# Power_management.net
KiCad netlist of a schematic drawn in Altium Designer
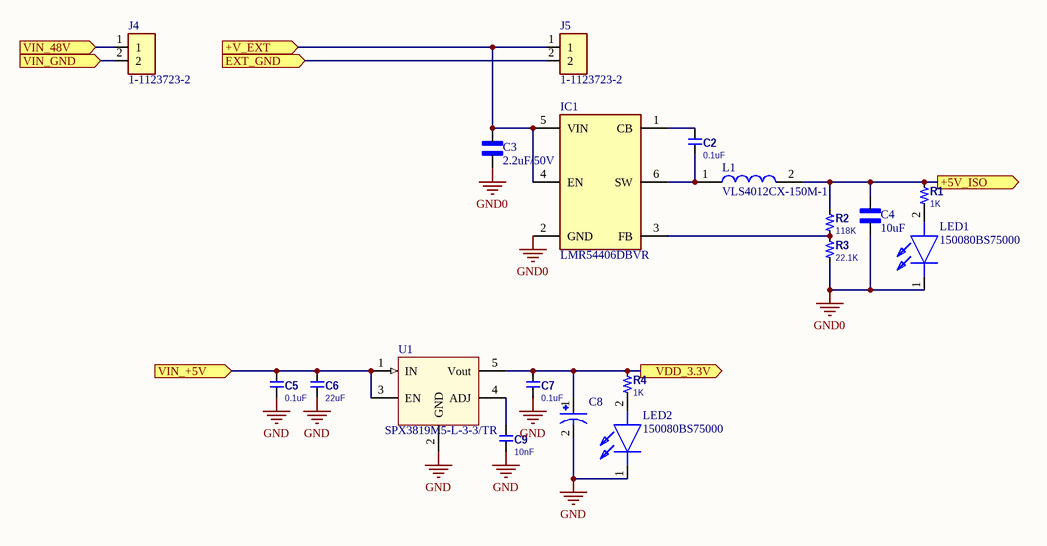
[diagram p0: Power_management.SchDoc]

(export (version "E")
  (design (tool "Eeschema 10.0.6"))
  (components
    (comp (ref "C2")
      (value "0.1uF")
      (footprint "0603-C")
      (description "CAP")
      (fields
        (field (name "MANUFACTURER") "TDK EPCOS")
        (field (name "MANUFACTURER PART NUMBER") "B37941K9105K62")
      )
      (libsource (lib "ESP32_IO_module") (part "CAP"))
    )
    (comp (ref "C3")
      (value "2.2uF/50V")
      (footprint "0805_C")
      (fields (field (name "MP") "LD03ZD475MAB2A"))
      (libsource (lib "IIOT_GATEWAY_MT7621") (part "CAP"))
    )
    (comp (ref "C4")
      (value "10uF")
      (footprint "0805_C")
      (fields (field (name "MP") "LD03ZD475MAB2A"))
      (libsource (lib "IIOT_GATEWAY_MT7621") (part "CAP"))
    )
    (comp (ref "C5")
      (value "0.1uF")
      (footprint "0603-C")
      (description "CAP")
      (fields
        (field (name "MANUFACTURER") "TDK EPCOS")
        (field (name "MANUFACTURER PART NUMBER") "B37941K9105K62")
      )
      (libsource (lib "Safety_Lock") (part "CAP"))
    )
    (comp (ref "C6")
      (value "22uF")
      (footprint "0603-C")
      (description "CAP")
      (fields
        (field (name "MANUFACTURER") "TDK EPCOS")
        (field (name "MANUFACTURER PART NUMBER") "B37941K9105K62")
      )
      (libsource (lib "Safety_Lock") (part "CAP"))
    )
    (comp (ref "C7")
      (value "0.1uF")
      (footprint "0603-C")
      (description "CAP")
      (fields
        (field (name "MANUFACTURER") "TDK EPCOS")
        (field (name "MANUFACTURER PART NUMBER") "B37941K9105K62")
      )
      (libsource (lib "Safety_Lock") (part "CAP"))
    )
    (comp (ref "C8")
      (value "T493X227K010BH6420_220uF")
      (footprint "CAPPM7343X430N")
      (fields (field (name "MP") "T493X227K010BH6420") (field (name "MF") "Kemet"))
      (libsource (lib "Safety_Lock") (part "T493X227K010BH6420_220uF"))
    )
    (comp (ref "C9")
      (value "10nF")
      (footprint "0603-C")
      (description "CAP")
      (fields
        (field (name "MANUFACTURER") "TDK EPCOS")
        (field (name "MANUFACTURER PART NUMBER") "B37941K9105K62")
      )
      (libsource (lib "Safety_Lock") (part "CAP"))
    )
    (comp (ref "IC1")
      (value "LMR54406DBVR")
      (footprint "SamacSys:SOT95P280X145-6N")
      (description "Integrated Circuit")
      (fields (field (name "MOUSER PART NUMBER") "595-LMR54406DBVR"))
      (libsource (lib "SamacSys") (part "LMR54406DBVR"))
    )
    (comp (ref "J4")
      (value "1-1123723-2")
      (footprint "TE_1-1123723-2")
      (description "3.96 EP HDR ASSY 2P_NATURAL_")
      (fields (field (name "MF") "TE Connectivity") (field (name "DIGI-KEY_PART_NUMBER") "A111830-ND"))
      (libsource (lib "IIOT_GATEWAY_MT7621") (part "1-1123723-2"))
    )
    (comp (ref "J5")
      (value "1-1123723-2")
      (footprint "TE_1-1123723-2")
      (description "3.96 EP HDR ASSY 2P_NATURAL_")
      (fields (field (name "MF") "TE Connectivity") (field (name "DIGI-KEY_PART_NUMBER") "A111830-ND"))
      (libsource (lib "IIOT_GATEWAY_MT7621") (part "1-1123723-2"))
    )
    (comp (ref "L1")
      (value "VLS4012CX-150M-1")
      (footprint "SamacSys:VLS4012")
      (description "Inductor")
      (fields (field (name "MOUSER PART NUMBER") "810-VLS4012CX150M1"))
      (libsource (lib "*") (part "VLS4012CX-150M-1"))
    )
    (comp (ref "LED1")
      (value "150080BS75000")
      (footprint "SamacSys:LEDC2012X80N")
      (description "LED")
      (fields (field (name "MOUSER PART NUMBER") "710-150080BS75000"))
      (libsource (lib "*") (part "150080BS75000"))
    )
    (comp (ref "LED2")
      (value "150080BS75000")
      (footprint "SamacSys:LEDC2012X80N")
      (description "LED")
      (fields (field (name "MOUSER PART NUMBER") "710-150080BS75000"))
      (libsource (lib "*") (part "150080BS75000"))
    )
    (comp (ref "R1")
      (value "1K")
      (footprint "0603-R")
      (fields
        (field (name "MANUFACTURER") "Panasonic")
        (field (name "MANUFACTURER PART NUMBER") "ERJ-8GEYJ621V")
        (field (name "TOLERANCE") "5%")
      )
      (libsource (lib "ESP32_IO_module") (part "Res_2"))
    )
    (comp (ref "R2")
      (value "118K")
      (footprint "0603-R")
      (fields
        (field (name "MANUFACTURER") "Panasonic")
        (field (name "MANUFACTURER PART NUMBER") "ERJ-8GEYJ621V")
        (field (name "TOLERANCE") "5%")
      )
      (libsource (lib "ESP32_IO_module") (part "Res_2"))
    )
    (comp (ref "R3")
      (value "22.1K")
      (footprint "0603-R")
      (fields
        (field (name "MANUFACTURER") "Panasonic")
        (field (name "MANUFACTURER PART NUMBER") "ERJ-8GEYJ621V")
        (field (name "TOLERANCE") "5%")
      )
      (libsource (lib "ESP32_IO_module") (part "Res_2"))
    )
    (comp (ref "R4")
      (value "1K")
      (footprint "0603-R")
      (fields
        (field (name "MANUFACTURER") "Panasonic")
        (field (name "MANUFACTURER PART NUMBER") "ERJ-8GEYJ621V")
        (field (name "TOLERANCE") "5%")
      )
      (libsource (lib "ESP32_IO_module") (part "Res_2"))
    )
    (comp (ref "U1")
      (value "SPX3819M5-L-3-3/TR")
      (footprint "SOT23-5")
      (description "Linear Voltage Regulator IC 1 Output 500mA SOT-23-5")
      (fields (field (name "MP") "SPX3819") (field (name "MF") "MaxLinear, Inc."))
      (libsource (lib "Safety_Lock") (part "SPX3819"))
    )
  )
  (nets
    (net (code "1") (name "/+5V_ISO") (class "Default")
      (node (ref "C4") (pin "1") (pinfunction "1_1") (pintype "passive"))
      (node (ref "L1") (pin "2") (pinfunction "2_2") (pintype "passive"))
      (node (ref "R1") (pin "2") (pinfunction "2_2") (pintype "passive"))
      (node (ref "R2") (pin "2") (pinfunction "2_2") (pintype "passive"))
    )
    (net (code "2") (name "/+V_EXT") (class "Default")
      (node (ref "C3") (pin "1") (pinfunction "1_1") (pintype "passive"))
      (node (ref "IC1") (pin "4") (pinfunction "EN_4") (pintype "passive"))
      (node (ref "IC1") (pin "5") (pinfunction "VIN_5") (pintype "passive"))
      (node (ref "J5") (pin "1") (pinfunction "1_1") (pintype "passive"))
    )
    (net (code "3") (name "/EXT_GND") (class "Default")
      (node (ref "J5") (pin "2") (pinfunction "2_2") (pintype "passive"))
    )
    (net (code "4") (name "/VDD_3.3V") (class "Default")
      (node (ref "C7") (pin "1") (pinfunction "1_1") (pintype "passive"))
      (node (ref "C8") (pin "1") (pinfunction "1_1") (pintype "passive"))
      (node (ref "R4") (pin "2") (pinfunction "2_2") (pintype "passive"))
      (node (ref "U1") (pin "5") (pinfunction "Vout_5") (pintype "passive"))
    )
    (net (code "5") (name "/VIN_+5V") (class "Default")
      (node (ref "C5") (pin "1") (pinfunction "1_1") (pintype "passive"))
      (node (ref "C6") (pin "1") (pinfunction "1_1") (pintype "passive"))
      (node (ref "U1") (pin "1") (pinfunction "IN_1") (pintype "input"))
      (node (ref "U1") (pin "3") (pinfunction "EN_3") (pintype "passive"))
    )
    (net (code "6") (name "/VIN_48V") (class "Default")
      (node (ref "J4") (pin "1") (pinfunction "1_1") (pintype "passive"))
    )
    (net (code "7") (name "/VIN_GND") (class "Default")
      (node (ref "J4") (pin "2") (pinfunction "2_2") (pintype "passive"))
    )
    (net (code "8") (name "GND") (class "Default")
      (node (ref "C5") (pin "2") (pinfunction "2_2") (pintype "passive"))
      (node (ref "C6") (pin "2") (pinfunction "2_2") (pintype "passive"))
      (node (ref "C7") (pin "2") (pinfunction "2_2") (pintype "passive"))
      (node (ref "C8") (pin "2") (pinfunction "2_2") (pintype "passive"))
      (node (ref "C9") (pin "2") (pinfunction "2_2") (pintype "passive"))
      (node (ref "LED2") (pin "1") (pinfunction "K_1") (pintype "passive"))
      (node (ref "U1") (pin "2") (pinfunction "GND_2") (pintype "power_in"))
    )
    (net (code "9") (name "GND0") (class "Default")
      (node (ref "C3") (pin "2") (pinfunction "2_2") (pintype "passive"))
      (node (ref "C4") (pin "2") (pinfunction "2_2") (pintype "passive"))
      (node (ref "IC1") (pin "2") (pinfunction "GND_2") (pintype "passive"))
      (node (ref "LED1") (pin "1") (pinfunction "K_1") (pintype "passive"))
      (node (ref "R3") (pin "1") (pinfunction "1_1") (pintype "passive"))
    )
    (net (code "10") (name "Net-(IC1-CB)") (class "Default")
      (node (ref "C2") (pin "1") (pinfunction "1_1") (pintype "passive"))
      (node (ref "IC1") (pin "1") (pinfunction "CB_1") (pintype "passive"))
    )
    (net (code "11") (name "Net-(IC1-FB)") (class "Default")
      (node (ref "IC1") (pin "3") (pinfunction "FB_3") (pintype "passive"))
      (node (ref "R2") (pin "1") (pinfunction "1_1") (pintype "passive"))
      (node (ref "R3") (pin "2") (pinfunction "2_2") (pintype "passive"))
    )
    (net (code "12") (name "Net-(IC1-SW)") (class "Default")
      (node (ref "C2") (pin "2") (pinfunction "2_2") (pintype "passive"))
      (node (ref "IC1") (pin "6") (pinfunction "SW_6") (pintype "passive"))
      (node (ref "L1") (pin "1") (pinfunction "1_1") (pintype "passive"))
    )
    (net (code "13") (name "Net-(LED1-A)") (class "Default")
      (node (ref "LED1") (pin "2") (pinfunction "A_2") (pintype "passive"))
      (node (ref "R1") (pin "1") (pinfunction "1_1") (pintype "passive"))
    )
    (net (code "14") (name "Net-(LED2-A)") (class "Default")
      (node (ref "LED2") (pin "2") (pinfunction "A_2") (pintype "passive"))
      (node (ref "R4") (pin "1") (pinfunction "1_1") (pintype "passive"))
    )
    (net (code "15") (name "Net-(U1-ADJ)") (class "Default")
      (node (ref "C9") (pin "1") (pinfunction "1_1") (pintype "passive"))
      (node (ref "U1") (pin "4") (pinfunction "ADJ_4") (pintype "passive"))
    )
  )
)
